# 2_-BUTTONS_ILLUMINATION.net
KiCad netlist of a schematic drawn in Altium Designer
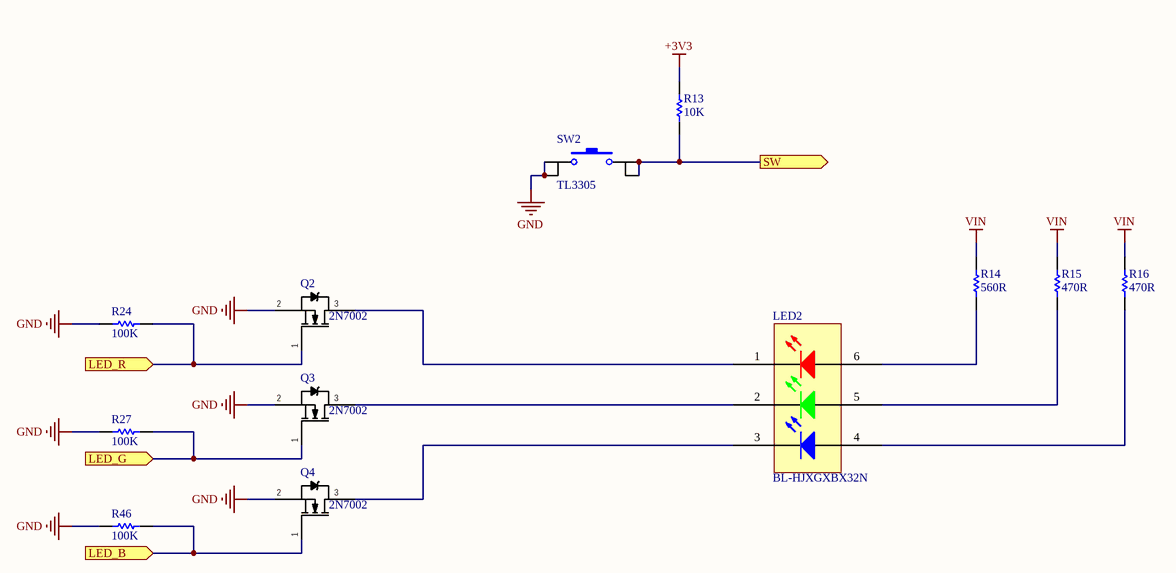
[diagram p0: [2]-BUTTONS_ILLUMINATION.SchDoc]

(export (version "E")
  (design (tool "Eeschema 10.0.6"))
  (components
    (comp (ref "LED2")
      (value "BL-HJXGXBX32N")
      (footprint "BL-HJXGXBX32N")
      (description "LED RGB 6PLCC SMD")
      (libsource (lib "bitsnio") (part "BL-HJXGXBX32N"))
    )
    (comp (ref "Q2")
      (value "2N7002")
      (footprint "SOT23-3N")
      (description "MOSFET N-CH 60V 115MA SOT-23")
      (fields (field (name "VOLTAGE") "60V"))
      (libsource (lib "bitsnio") (part "2N7002"))
    )
    (comp (ref "Q3")
      (value "2N7002")
      (footprint "SOT23-3N")
      (description "MOSFET N-CH 60V 115MA SOT-23")
      (fields (field (name "VOLTAGE") "60V"))
      (libsource (lib "bitsnio") (part "2N7002"))
    )
    (comp (ref "Q4")
      (value "2N7002")
      (footprint "SOT23-3N")
      (description "MOSFET N-CH 60V 115MA SOT-23")
      (fields (field (name "VOLTAGE") "60V"))
      (libsource (lib "bitsnio") (part "2N7002"))
    )
    (comp (ref "R13")
      (value "10K")
      (footprint "RESC1608N")
      (description "RES SMD 10K OHM 5% 1/10W 0603")
      (fields (field (name "TOLERANCE") "5%"))
      (libsource (lib "bitsnio") (part "AC0603JR-0710KL"))
    )
    (comp (ref "R14")
      (value "560R")
      (footprint "RESC1608N")
      (description "RES SMD 560 OHM 5% 1/10W 0603")
      (fields (field (name "TOLERANCE") "5%"))
      (libsource (lib "bitsnio") (part "AC0603JR-07560RL"))
    )
    (comp (ref "R15")
      (value "470R")
      (footprint "RESC1608N")
      (description "RES SMD 470 OHM 5% 1/10W 0603")
      (fields (field (name "TOLERANCE") "5%"))
      (libsource (lib "bitsnio") (part "RMCF0603JT470R"))
    )
    (comp (ref "R16")
      (value "470R")
      (footprint "RESC1608N")
      (description "RES SMD 470 OHM 5% 1/10W 0603")
      (fields (field (name "TOLERANCE") "5%"))
      (libsource (lib "bitsnio") (part "RMCF0603JT470R"))
    )
    (comp (ref "R24")
      (value "100K")
      (footprint "RESC1608N")
      (description "RES SMD 100K OHM 5% 1/4W 0603")
      (fields (field (name "TOLERANCE") "5%"))
      (libsource (lib "bitsnio") (part "ESR03EZPJ104"))
    )
    (comp (ref "R27")
      (value "100K")
      (footprint "RESC1608N")
      (description "RES SMD 100K OHM 5% 1/4W 0603")
      (fields (field (name "TOLERANCE") "5%"))
      (libsource (lib "bitsnio") (part "ESR03EZPJ104"))
    )
    (comp (ref "R46")
      (value "100K")
      (footprint "RESC1608N")
      (description "RES SMD 100K OHM 5% 1/4W 0603")
      (fields (field (name "TOLERANCE") "5%"))
      (libsource (lib "bitsnio") (part "ESR03EZPJ104"))
    )
    (comp (ref "SW2")
      (value "TL3305")
      (footprint "TL3305")
      (description "SWITCH TACTILE SPST-NO 50MA 12V")
      (libsource (lib "bitsnio") (part "TL3305AF160QG"))
    )
  )
  (nets
    (net (code "1") (name "+3V3") (class "Default")
      (node (ref "R13") (pin "2") (pinfunction "2_2") (pintype "passive"))
    )
    (net (code "2") (name "/LED_B") (class "Default")
      (node (ref "Q4") (pin "1") (pinfunction "G_1") (pintype "passive"))
      (node (ref "R46") (pin "1") (pinfunction "1_1") (pintype "passive"))
    )
    (net (code "3") (name "/LED_G") (class "Default")
      (node (ref "Q3") (pin "1") (pinfunction "G_1") (pintype "passive"))
      (node (ref "R27") (pin "1") (pinfunction "1_1") (pintype "passive"))
    )
    (net (code "4") (name "/LED_R") (class "Default")
      (node (ref "Q2") (pin "1") (pinfunction "G_1") (pintype "passive"))
      (node (ref "R24") (pin "1") (pinfunction "1_1") (pintype "passive"))
    )
    (net (code "5") (name "/SW") (class "Default")
      (node (ref "R13") (pin "1") (pinfunction "1_1") (pintype "passive"))
      (node (ref "SW2") (pin "3") (pinfunction "3_3") (pintype "passive"))
      (node (ref "SW2") (pin "4") (pinfunction "4_4") (pintype "passive"))
    )
    (net (code "6") (name "GND") (class "Default")
      (node (ref "Q2") (pin "2") (pinfunction "S_2") (pintype "passive"))
      (node (ref "Q3") (pin "2") (pinfunction "S_2") (pintype "passive"))
      (node (ref "Q4") (pin "2") (pinfunction "S_2") (pintype "passive"))
      (node (ref "R24") (pin "2") (pinfunction "2_2") (pintype "passive"))
      (node (ref "R27") (pin "2") (pinfunction "2_2") (pintype "passive"))
      (node (ref "R46") (pin "2") (pinfunction "2_2") (pintype "passive"))
      (node (ref "SW2") (pin "1") (pinfunction "1_1") (pintype "passive"))
      (node (ref "SW2") (pin "2") (pinfunction "2_2") (pintype "passive"))
    )
    (net (code "7") (name "Net-(LED2-Pad4)") (class "Default")
      (node (ref "LED2") (pin "4") (pinfunction "4_4") (pintype "passive"))
      (node (ref "R16") (pin "1") (pinfunction "1_1") (pintype "passive"))
    )
    (net (code "8") (name "Net-(LED2-Pad5)") (class "Default")
      (node (ref "LED2") (pin "5") (pinfunction "5_5") (pintype "passive"))
      (node (ref "R15") (pin "1") (pinfunction "1_1") (pintype "passive"))
    )
    (net (code "9") (name "Net-(LED2-Pad6)") (class "Default")
      (node (ref "LED2") (pin "6") (pinfunction "6_6") (pintype "passive"))
      (node (ref "R14") (pin "1") (pinfunction "1_1") (pintype "passive"))
    )
    (net (code "10") (name "Net-(Q2-D)") (class "Default")
      (node (ref "LED2") (pin "1") (pinfunction "1_1") (pintype "passive"))
      (node (ref "Q2") (pin "3") (pinfunction "D_3") (pintype "passive"))
    )
    (net (code "11") (name "Net-(Q3-D)") (class "Default")
      (node (ref "LED2") (pin "2") (pinfunction "2_2") (pintype "passive"))
      (node (ref "Q3") (pin "3") (pinfunction "D_3") (pintype "passive"))
    )
    (net (code "12") (name "Net-(Q4-D)") (class "Default")
      (node (ref "LED2") (pin "3") (pinfunction "3_3") (pintype "passive"))
      (node (ref "Q4") (pin "3") (pinfunction "D_3") (pintype "passive"))
    )
    (net (code "13") (name "VIN") (class "Default")
      (node (ref "R14") (pin "2") (pinfunction "2_2") (pintype "passive"))
      (node (ref "R15") (pin "2") (pinfunction "2_2") (pintype "passive"))
      (node (ref "R16") (pin "2") (pinfunction "2_2") (pintype "passive"))
    )
  )
)
